# tracer-main.net
KiCad netlist of a schematic drawn in EAGLE
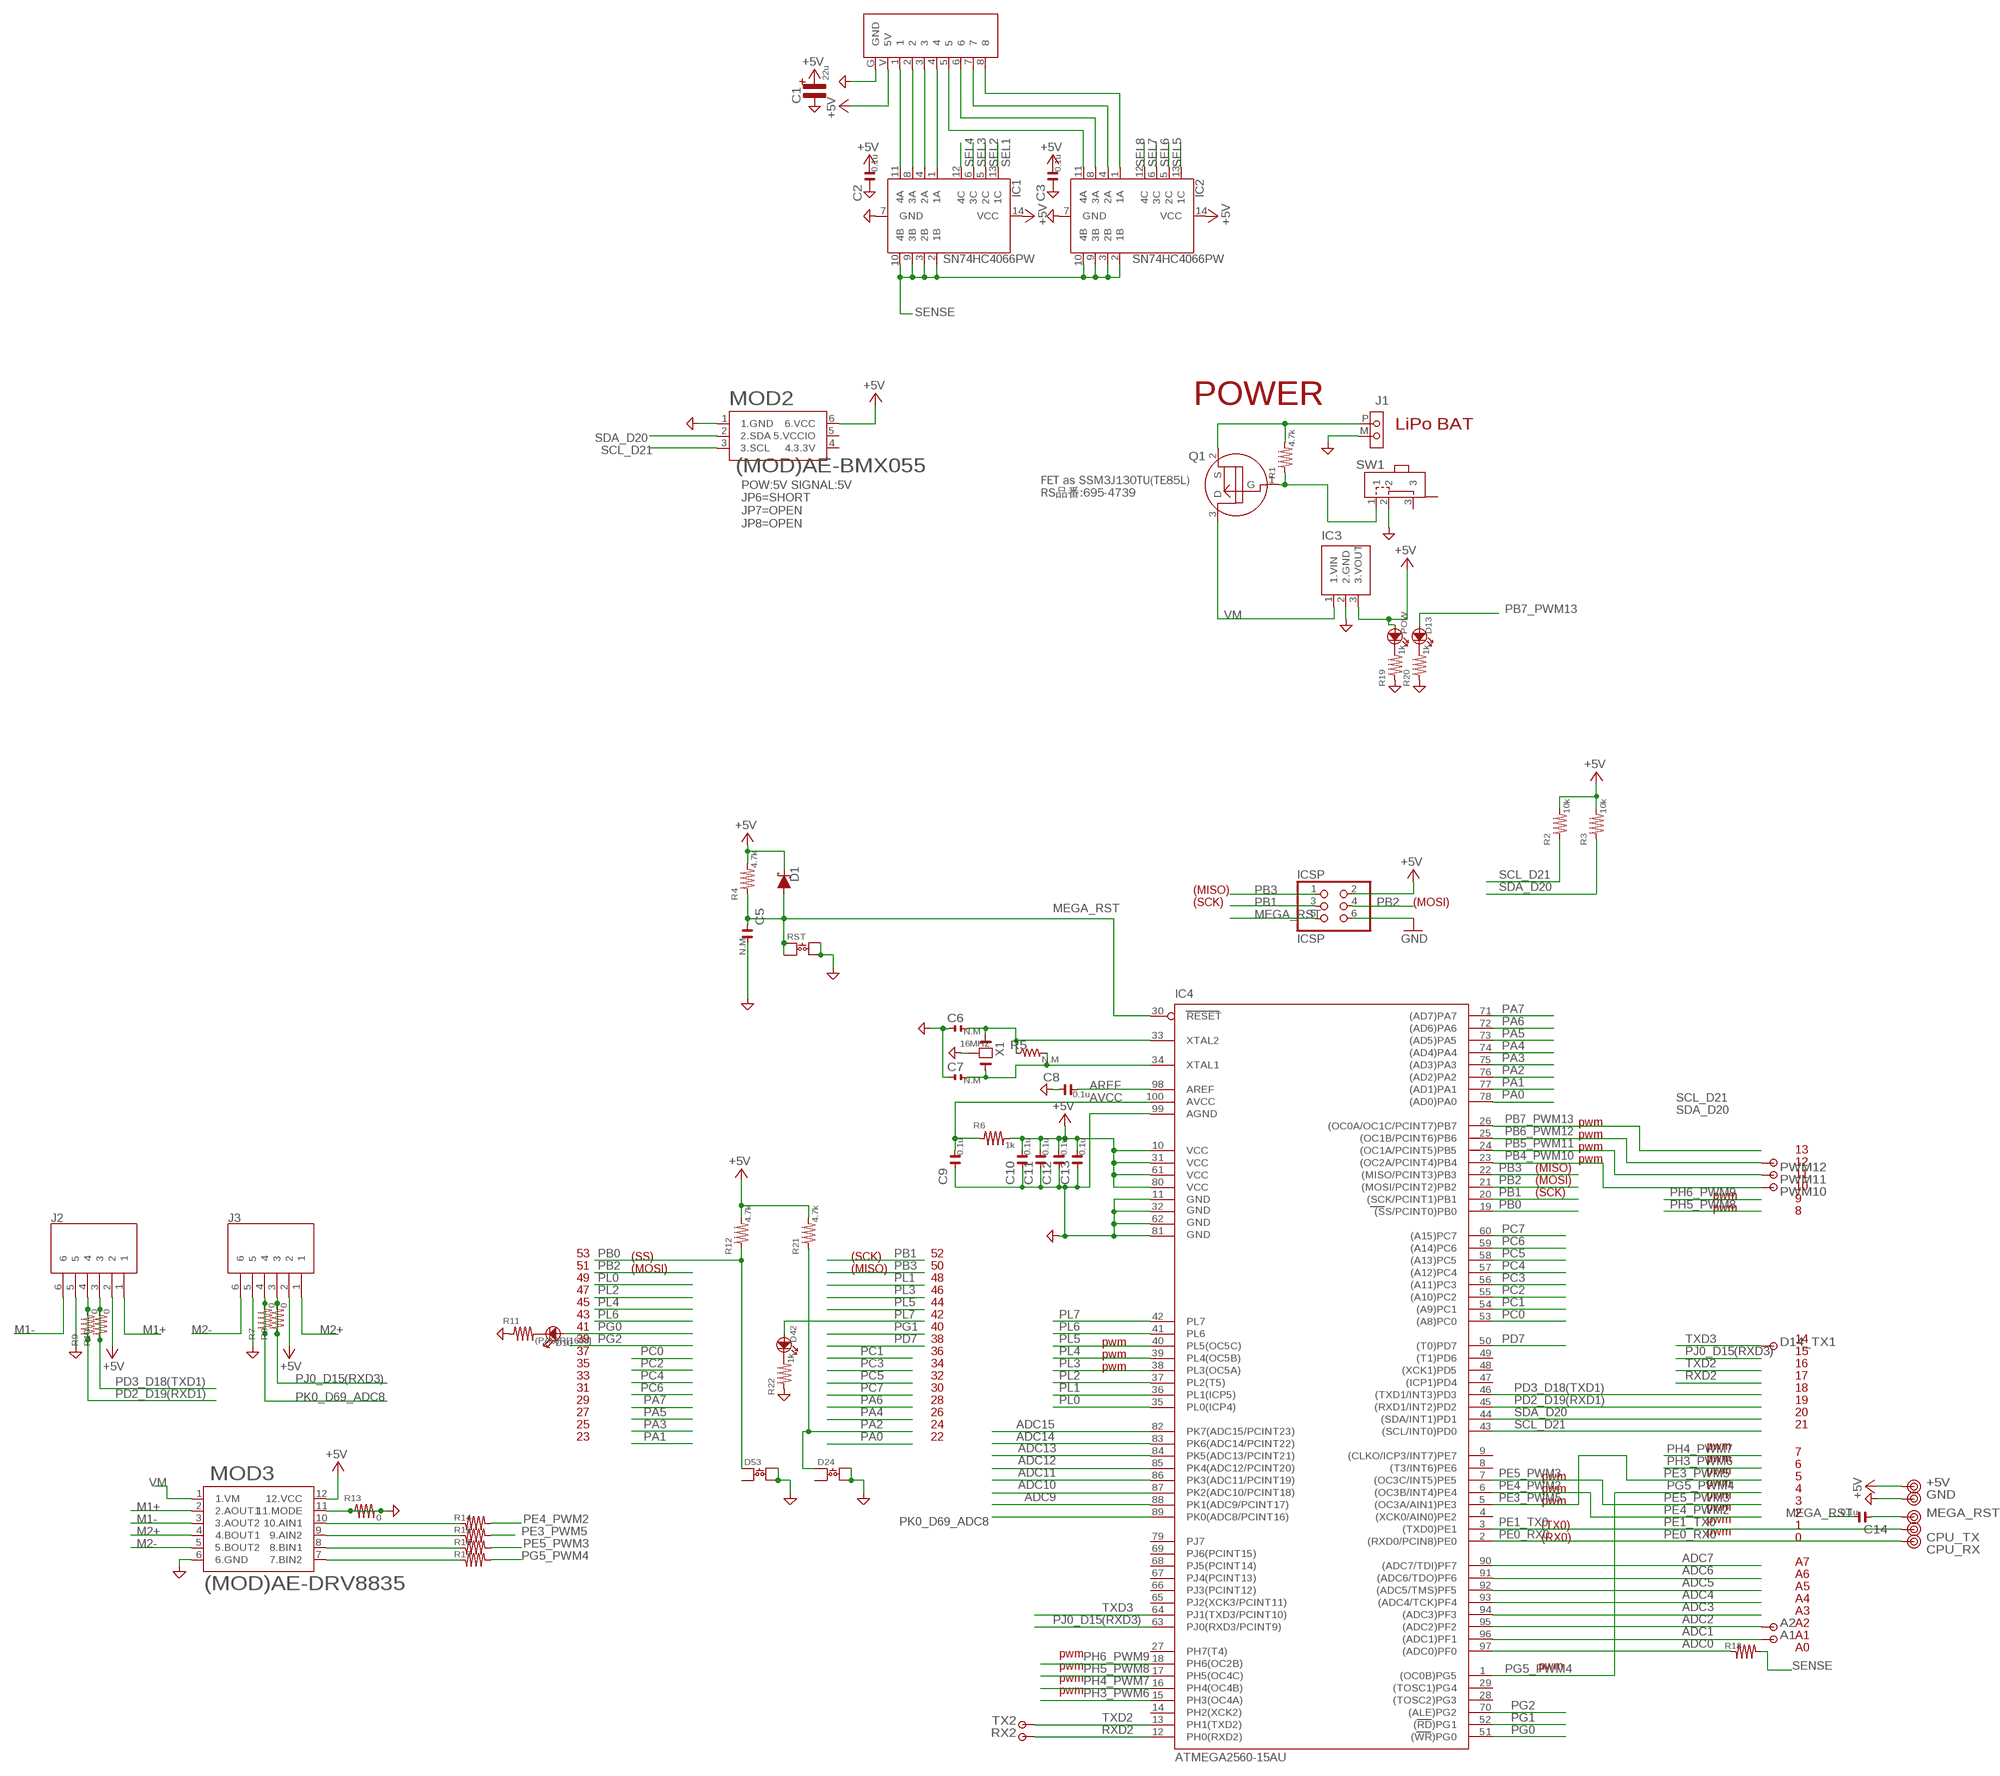
[diagram p0: schematic, sheet 1]

(export (version "E")
  (design (tool "Eeschema 10.0.6"))
  (components
    (comp (ref "+5V")
      (value "TP-HOLE")
      (footprint "eagle-import:TP-HOLE")
      (libsource (lib "eagle-import") (part "TP-HOLE"))
    )
    (comp (ref "A1")
      (value "TP")
      (footprint "eagle-import:TP-SQUARE")
      (libsource (lib "eagle-import") (part "TP"))
    )
    (comp (ref "A2")
      (value "TP")
      (footprint "eagle-import:TP-SQUARE")
      (libsource (lib "eagle-import") (part "TP"))
    )
    (comp (ref "C1")
      (value "22u")
      (footprint "eagle-import:3216")
      (libsource (lib "eagle-import") (part "(PAS)C[3216]"))
    )
    (comp (ref "C2")
      (value "0.1u")
      (footprint "eagle-import:1608NEW")
      (libsource (lib "eagle-import") (part "(PAS)C[1608]"))
    )
    (comp (ref "C3")
      (value "0.1u")
      (footprint "eagle-import:1608NEW")
      (libsource (lib "eagle-import") (part "(PAS)C[1608]"))
    )
    (comp (ref "C5")
      (value "N.M")
      (footprint "eagle-import:1608NEW")
      (libsource (lib "eagle-import") (part "(PAS)C[1608]"))
    )
    (comp (ref "C6")
      (value "N.M")
      (footprint "eagle-import:1005")
      (libsource (lib "eagle-import") (part "C(1005)"))
    )
    (comp (ref "C7")
      (value "N.M")
      (footprint "eagle-import:1005")
      (libsource (lib "eagle-import") (part "C(1005)"))
    )
    (comp (ref "C8")
      (value "0.1u")
      (footprint "eagle-import:1608NEW")
      (libsource (lib "eagle-import") (part "(PAS)C[1608]"))
    )
    (comp (ref "C9")
      (value "0.1u")
      (footprint "eagle-import:1608NEW")
      (libsource (lib "eagle-import") (part "(PAS)C[1608]"))
    )
    (comp (ref "C10")
      (value "0.1u")
      (footprint "eagle-import:1608NEW")
      (libsource (lib "eagle-import") (part "(PAS)C[1608]"))
    )
    (comp (ref "C11")
      (value "0.1u")
      (footprint "eagle-import:1608NEW")
      (libsource (lib "eagle-import") (part "(PAS)C[1608]"))
    )
    (comp (ref "C12")
      (value "0.1u")
      (footprint "eagle-import:1608NEW")
      (libsource (lib "eagle-import") (part "(PAS)C[1608]"))
    )
    (comp (ref "C13")
      (value "0.1u")
      (footprint "eagle-import:1608NEW")
      (libsource (lib "eagle-import") (part "(PAS)C[1608]"))
    )
    (comp (ref "C14")
      (value "0.1u")
      (footprint "eagle-import:1608NEW")
      (libsource (lib "eagle-import") (part "(PAS)C[1608]"))
    )
    (comp (ref "CPU_RX")
      (value "TP-HOLE")
      (footprint "eagle-import:TP-HOLE")
      (libsource (lib "eagle-import") (part "TP-HOLE"))
    )
    (comp (ref "CPU_TX")
      (value "TP-HOLE")
      (footprint "eagle-import:TP-HOLE")
      (libsource (lib "eagle-import") (part "TP-HOLE"))
    )
    (comp (ref "D1")
      (value "1A/23V/620mV")
      (footprint "eagle-import:SOD-323")
      (libsource (lib "eagle-import") (part "DIODE-SCHOTTKY-BAT20J"))
    )
    (comp (ref "D10")
      (value "(PAS)LED[1608]")
      (footprint "eagle-import:1608LED")
      (libsource (lib "eagle-import") (part "(PAS)LED[1608]"))
    )
    (comp (ref "D13")
      (value "(PAS)LED[1608]")
      (footprint "eagle-import:1608LED")
      (libsource (lib "eagle-import") (part "(PAS)LED[1608]"))
    )
    (comp (ref "D14_TX1")
      (value "TP")
      (footprint "eagle-import:TP-SQUARE")
      (libsource (lib "eagle-import") (part "TP"))
    )
    (comp (ref "D24")
      (value "(SW)USER_SW(AKIDUKI)")
      (footprint "eagle-import:SKRPACE010-PAC")
      (libsource (lib "eagle-import") (part "(SW)USER_SW(AKIDUKI)"))
    )
    (comp (ref "D42")
      (value "(PAS)LED[1608]")
      (footprint "eagle-import:1608LED")
      (libsource (lib "eagle-import") (part "(PAS)LED[1608]"))
    )
    (comp (ref "D53")
      (value "(SW)USER_SW(AKIDUKI)")
      (footprint "eagle-import:SKRPACE010-PAC")
      (libsource (lib "eagle-import") (part "(SW)USER_SW(AKIDUKI)"))
    )
    (comp (ref "GND")
      (value "TP-HOLE")
      (footprint "eagle-import:TP-HOLE")
      (libsource (lib "eagle-import") (part "TP-HOLE"))
    )
    (comp (ref "IC1")
      (value "SN74HC4066PW")
      (footprint "eagle-import:SOP65P640X120-14N")
      (fields (field (name "RS_PART_NUMBER") "6622738P"))
      (libsource (lib "eagle-import") (part "SN74HC4066PW"))
    )
    (comp (ref "IC2")
      (value "SN74HC4066PW")
      (footprint "eagle-import:SOP65P640X120-14N")
      (fields (field (name "RS_PART_NUMBER") "6622738P"))
      (libsource (lib "eagle-import") (part "SN74HC4066PW"))
    )
    (comp (ref "IC3")
      (value "(3.3V)VX07803-500")
      (footprint "eagle-import:VX07803-PAC")
      (libsource (lib "eagle-import") (part "(3.3V)VX07803-500"))
    )
    (comp (ref "IC4")
      (value "ATMEGA2560-15AU")
      (footprint "eagle-import:TQFP100")
      (fields (field (name "PART_NUMBER") "ATMEGA2560-16AU"))
      (libsource (lib "eagle-import") (part "0023_ATMEGA2560-16AU"))
    )
    (comp (ref "ICSP")
      (value "ICSP")
      (footprint "eagle-import:2X03")
      (fields (field (name "PART_NUMBER") "PH254-203DF118A00V"))
      (libsource (lib "eagle-import") (part "0114_PH254-203DF118A00V"))
    )
    (comp (ref "J1")
      (value "B2B-PH")
      (footprint "eagle-import:B2B-PH-PAC")
      (libsource (lib "eagle-import") (part "B2B-PH"))
    )
    (comp (ref "J2")
      (value "B6B-ZR-3.4_LF__SN_")
      (footprint "eagle-import:B6BZR34LFSN")
      (fields (field (name "MANUFACTURER_PART_NUMBER") "B6B-ZR-3.4(LF)(SN)"))
      (libsource (lib "eagle-import") (part "B6B-ZR-3.4_LF__SN_"))
    )
    (comp (ref "J3")
      (value "B6B-ZR-3.4_LF__SN_")
      (footprint "eagle-import:B6BZR34LFSN")
      (fields (field (name "MANUFACTURER_PART_NUMBER") "B6B-ZR-3.4(LF)(SN)"))
      (libsource (lib "eagle-import") (part "B6B-ZR-3.4_LF__SN_"))
    )
    (comp (ref "MEGA_RST")
      (value "TP-HOLE")
      (footprint "eagle-import:TP-HOLE")
      (libsource (lib "eagle-import") (part "TP-HOLE"))
    )
    (comp (ref "MOD1")
      (value "(MOD)LINE-TRACER")
      (footprint "eagle-import:8CH-LINETRACER-MOD")
      (libsource (lib "eagle-import") (part "(MOD)LINE-TRACER"))
    )
    (comp (ref "MOD2")
      (value "(MOD)AE-BMX055")
      (footprint "eagle-import:MOD-BMX055")
      (libsource (lib "eagle-import") (part "(MOD)AE-BMX055"))
    )
    (comp (ref "MOD3")
      (value "(MOD)AE-DRV8835")
      (footprint "eagle-import:AE-DRV8835")
      (libsource (lib "eagle-import") (part "(MOD)AE-DRV8835"))
    )
    (comp (ref "POW")
      (value "(PAS)LED[1608]")
      (footprint "eagle-import:1608LED")
      (libsource (lib "eagle-import") (part "(PAS)LED[1608]"))
    )
    (comp (ref "PWM10")
      (value "TP")
      (footprint "eagle-import:TP-SQUARE")
      (libsource (lib "eagle-import") (part "TP"))
    )
    (comp (ref "PWM11")
      (value "TP")
      (footprint "eagle-import:TP-SQUARE")
      (libsource (lib "eagle-import") (part "TP"))
    )
    (comp (ref "PWM12")
      (value "TP")
      (footprint "eagle-import:TP-SQUARE")
      (libsource (lib "eagle-import") (part "TP"))
    )
    (comp (ref "Q1")
      (value "FET-PCH(SSM3J130TU)")
      (footprint "eagle-import:SOT65P210X75-3N")
      (fields
        (field (name "MANUFACTURER_PART_NUMBER") "SSM3J130TU(TE85L)")
        (field (name "RS_PART_NUMBER") "6954739")
      )
      (libsource (lib "eagle-import") (part "FET-PCH(SSM3J130TU)"))
    )
    (comp (ref "R1")
      (value "4.7k")
      (footprint "eagle-import:1608NEW")
      (libsource (lib "eagle-import") (part "(PAS)R[1608]"))
    )
    (comp (ref "R2")
      (value "10k")
      (footprint "eagle-import:1608NEW")
      (libsource (lib "eagle-import") (part "(PAS)R[1608]"))
    )
    (comp (ref "R3")
      (value "10k")
      (footprint "eagle-import:1608NEW")
      (libsource (lib "eagle-import") (part "(PAS)R[1608]"))
    )
    (comp (ref "R4")
      (value "4.7k")
      (footprint "eagle-import:1608NEW")
      (libsource (lib "eagle-import") (part "(PAS)R[1608]"))
    )
    (comp (ref "R5")
      (value "N.M")
      (footprint "eagle-import:1005")
      (libsource (lib "eagle-import") (part "R(1005)"))
    )
    (comp (ref "R6")
      (value "1k")
      (footprint "eagle-import:1608NEW")
      (libsource (lib "eagle-import") (part "(PAS)R[1608]"))
    )
    (comp (ref "R7")
      (value "0")
      (footprint "eagle-import:1608NEW")
      (libsource (lib "eagle-import") (part "(PAS)R[1608]"))
    )
    (comp (ref "R8")
      (value "0")
      (footprint "eagle-import:1608NEW")
      (libsource (lib "eagle-import") (part "(PAS)R[1608]"))
    )
    (comp (ref "R9")
      (value "0")
      (footprint "eagle-import:1608NEW")
      (libsource (lib "eagle-import") (part "(PAS)R[1608]"))
    )
    (comp (ref "R10")
      (value "0")
      (footprint "eagle-import:1608NEW")
      (libsource (lib "eagle-import") (part "(PAS)R[1608]"))
    )
    (comp (ref "R11")
      (value "(PAS)R[1608]")
      (footprint "eagle-import:1608NEW")
      (libsource (lib "eagle-import") (part "(PAS)R[1608]"))
    )
    (comp (ref "R12")
      (value "4.7k")
      (footprint "eagle-import:1608NEW")
      (libsource (lib "eagle-import") (part "(PAS)R[1608]"))
    )
    (comp (ref "R13")
      (value "0")
      (footprint "eagle-import:1608NEW")
      (libsource (lib "eagle-import") (part "(PAS)R[1608]"))
    )
    (comp (ref "R14")
      (value "30")
      (footprint "eagle-import:1608NEW")
      (libsource (lib "eagle-import") (part "(PAS)R[1608]"))
    )
    (comp (ref "R15")
      (value "30")
      (footprint "eagle-import:1608NEW")
      (libsource (lib "eagle-import") (part "(PAS)R[1608]"))
    )
    (comp (ref "R16")
      (value "30")
      (footprint "eagle-import:1608NEW")
      (libsource (lib "eagle-import") (part "(PAS)R[1608]"))
    )
    (comp (ref "R17")
      (value "30")
      (footprint "eagle-import:1608NEW")
      (libsource (lib "eagle-import") (part "(PAS)R[1608]"))
    )
    (comp (ref "R18")
      (value "30")
      (footprint "eagle-import:1608NEW")
      (libsource (lib "eagle-import") (part "(PAS)R[1608]"))
    )
    (comp (ref "R19")
      (value "1k")
      (footprint "eagle-import:1608NEW")
      (libsource (lib "eagle-import") (part "(PAS)R[1608]"))
    )
    (comp (ref "R20")
      (value "1k")
      (footprint "eagle-import:1608NEW")
      (libsource (lib "eagle-import") (part "(PAS)R[1608]"))
    )
    (comp (ref "R21")
      (value "4.7k")
      (footprint "eagle-import:1608NEW")
      (libsource (lib "eagle-import") (part "(PAS)R[1608]"))
    )
    (comp (ref "R22")
      (value "1k")
      (footprint "eagle-import:1608NEW")
      (libsource (lib "eagle-import") (part "(PAS)R[1608]"))
    )
    (comp (ref "RST")
      (value "(SW)USER_SW(AKIDUKI)")
      (footprint "eagle-import:SKRPACE010-PAC")
      (libsource (lib "eagle-import") (part "(SW)USER_SW(AKIDUKI)"))
    )
    (comp (ref "RX2")
      (value "TP")
      (footprint "eagle-import:TP-SQUARE")
      (libsource (lib "eagle-import") (part "TP"))
    )
    (comp (ref "SW1")
      (value "MSK12C01")
      (footprint "eagle-import:MSK12C01")
      (libsource (lib "eagle-import") (part "MSK12C01"))
    )
    (comp (ref "TX2")
      (value "TP")
      (footprint "eagle-import:TP-SQUARE")
      (libsource (lib "eagle-import") (part "TP"))
    )
    (comp (ref "X1")
      (value "16MHZ")
      (footprint "eagle-import:AWSCR8")
      (libsource (lib "eagle-import") (part "(RESONATOR)CSTCE_10_12_16_20MHZ"))
    )
  )
  (nets
    (net (code "1") (name "+5V") (class "Default")
      (node (ref "+5V") (pin "1") (pinfunction "P$1_1") (pintype "passive"))
      (node (ref "C1") (pin "1") (pinfunction "P_1") (pintype "passive"))
      (node (ref "C10") (pin "2") (pinfunction "P$2_2") (pintype "passive"))
      (node (ref "C11") (pin "2") (pinfunction "P$2_2") (pintype "passive"))
      (node (ref "C12") (pin "2") (pinfunction "P$2_2") (pintype "passive"))
      (node (ref "C13") (pin "2") (pinfunction "P$2_2") (pintype "passive"))
      (node (ref "C2") (pin "2") (pinfunction "P$2_2") (pintype "passive"))
      (node (ref "C3") (pin "2") (pinfunction "P$2_2") (pintype "passive"))
      (node (ref "D1") (pin "C") (pinfunction "C_C") (pintype "passive"))
      (node (ref "IC1") (pin "14") (pinfunction "VCC_14") (pintype "passive"))
      (node (ref "IC2") (pin "14") (pinfunction "VCC_14") (pintype "passive"))
      (node (ref "IC3") (pin "3") (pinfunction "3.VOUT_3") (pintype "passive"))
      (node (ref "IC4") (pin "10") (pinfunction "VCC_10") (pintype "power_in"))
      (node (ref "IC4") (pin "31") (pinfunction "VCC1_31") (pintype "power_in"))
      (node (ref "IC4") (pin "61") (pinfunction "VCC2_61") (pintype "power_in"))
      (node (ref "IC4") (pin "80") (pinfunction "VCC3_80") (pintype "power_in"))
      (node (ref "ICSP") (pin "2") (pinfunction "2_2") (pintype "passive"))
      (node (ref "J2") (pin "2") (pinfunction "2_2") (pintype "bidirectional"))
      (node (ref "J3") (pin "2") (pinfunction "2_2") (pintype "bidirectional"))
      (node (ref "MOD1") (pin "V") (pinfunction "5V_V") (pintype "passive"))
      (node (ref "MOD2") (pin "6") (pinfunction "6.VCC_6") (pintype "passive"))
      (node (ref "MOD3") (pin "12") (pinfunction "12.VCC_12") (pintype "passive"))
      (node (ref "POW") (pin "1") (pinfunction "+_1") (pintype "passive"))
      (node (ref "R12") (pin "2") (pinfunction "2_2") (pintype "passive"))
      (node (ref "R2") (pin "2") (pinfunction "2_2") (pintype "passive"))
      (node (ref "R21") (pin "2") (pinfunction "2_2") (pintype "passive"))
      (node (ref "R3") (pin "2") (pinfunction "2_2") (pintype "passive"))
      (node (ref "R4") (pin "2") (pinfunction "2_2") (pintype "passive"))
      (node (ref "R6") (pin "2") (pinfunction "2_2") (pintype "passive"))
    )
    (net (code "2") (name "/ADC0") (class "Default")
      (node (ref "IC4") (pin "97") (pinfunction "(ADC0)PF0_97") (pintype "bidirectional"))
      (node (ref "R18") (pin "1") (pinfunction "1_1") (pintype "passive"))
    )
    (net (code "3") (name "/ADC1") (class "Default")
      (node (ref "A1") (pin "1") (pinfunction "P$1_1") (pintype "passive"))
      (node (ref "IC4") (pin "96") (pinfunction "(ADC1)PF1_96") (pintype "bidirectional"))
    )
    (net (code "4") (name "/ADC2") (class "Default")
      (node (ref "A2") (pin "1") (pinfunction "P$1_1") (pintype "passive"))
      (node (ref "IC4") (pin "95") (pinfunction "(ADC2)PF2_95") (pintype "bidirectional"))
    )
    (net (code "5") (name "/ADC3") (class "Default")
      (node (ref "IC4") (pin "94") (pinfunction "(ADC3)PF3_94") (pintype "bidirectional"))
    )
    (net (code "6") (name "/ADC4") (class "Default")
      (node (ref "IC4") (pin "93") (pinfunction "(ADC4/TCK)PF4_93") (pintype "bidirectional"))
    )
    (net (code "7") (name "/ADC5") (class "Default")
      (node (ref "IC4") (pin "92") (pinfunction "(ADC5/TMS)PF5_92") (pintype "bidirectional"))
    )
    (net (code "8") (name "/ADC6") (class "Default")
      (node (ref "IC4") (pin "91") (pinfunction "(ADC6/TDO)PF6_91") (pintype "bidirectional"))
    )
    (net (code "9") (name "/ADC7") (class "Default")
      (node (ref "IC4") (pin "90") (pinfunction "(ADC7/TDI)PF7_90") (pintype "bidirectional"))
    )
    (net (code "10") (name "/ADC9") (class "Default")
      (node (ref "IC4") (pin "88") (pinfunction "PK1(ADC9/PCINT17)_88") (pintype "bidirectional"))
    )
    (net (code "11") (name "/ADC10") (class "Default")
      (node (ref "IC4") (pin "87") (pinfunction "PK2(ADC10/PCINT18)_87") (pintype "bidirectional"))
    )
    (net (code "12") (name "/ADC11") (class "Default")
      (node (ref "IC4") (pin "86") (pinfunction "PK3(ADC11/PCINT19)_86") (pintype "bidirectional"))
    )
    (net (code "13") (name "/ADC12") (class "Default")
      (node (ref "IC4") (pin "85") (pinfunction "PK4(ADC12/PCINT20)_85") (pintype "bidirectional"))
    )
    (net (code "14") (name "/ADC13") (class "Default")
      (node (ref "IC4") (pin "84") (pinfunction "PK5(ADC13/PCINT21)_84") (pintype "bidirectional"))
    )
    (net (code "15") (name "/ADC14") (class "Default")
      (node (ref "IC4") (pin "83") (pinfunction "PK6(ADC14/PCINT22)_83") (pintype "bidirectional"))
    )
    (net (code "16") (name "/ADC15") (class "Default")
      (node (ref "IC4") (pin "82") (pinfunction "PK7(ADC15/PCINT23)_82") (pintype "bidirectional"))
    )
    (net (code "17") (name "/AREF") (class "Default")
      (node (ref "C8") (pin "2") (pinfunction "P$2_2") (pintype "passive"))
      (node (ref "IC4") (pin "98") (pinfunction "AREF_98") (pintype "bidirectional"))
    )
    (net (code "18") (name "/AVCC") (class "Default")
      (node (ref "C9") (pin "2") (pinfunction "P$2_2") (pintype "passive"))
      (node (ref "IC4") (pin "100") (pinfunction "AVCC_100") (pintype "power_in"))
      (node (ref "R6") (pin "1") (pinfunction "1_1") (pintype "passive"))
    )
    (net (code "19") (name "/M1+") (class "Default")
      (node (ref "J2") (pin "1") (pinfunction "1_1") (pintype "bidirectional"))
      (node (ref "MOD3") (pin "2") (pinfunction "2.AOUT1_2") (pintype "passive"))
    )
    (net (code "20") (name "/M1-") (class "Default")
      (node (ref "J2") (pin "6") (pinfunction "6_6") (pintype "bidirectional"))
      (node (ref "MOD3") (pin "3") (pinfunction "3.AOUT2_3") (pintype "passive"))
    )
    (net (code "21") (name "/M2+") (class "Default")
      (node (ref "J3") (pin "1") (pinfunction "1_1") (pintype "bidirectional"))
      (node (ref "MOD3") (pin "4") (pinfunction "4.BOUT1_4") (pintype "passive"))
    )
    (net (code "22") (name "/M2-") (class "Default")
      (node (ref "J3") (pin "6") (pinfunction "6_6") (pintype "bidirectional"))
      (node (ref "MOD3") (pin "5") (pinfunction "5.BOUT2_5") (pintype "passive"))
    )
    (net (code "23") (name "/MEGA_RST") (class "Default")
      (node (ref "C14") (pin "2") (pinfunction "P$2_2") (pintype "passive"))
      (node (ref "C5") (pin "1") (pinfunction "P$1_1") (pintype "passive"))
      (node (ref "D1") (pin "A") (pinfunction "A_A") (pintype "passive"))
      (node (ref "IC4") (pin "30") (pinfunction "RESET_30") (pintype "input"))
      (node (ref "ICSP") (pin "5") (pinfunction "5_5") (pintype "passive"))
      (node (ref "R4") (pin "1") (pinfunction "1_1") (pintype "passive"))
      (node (ref "RST") (pin "1") (pinfunction "1_1") (pintype "passive"))
      (node (ref "RST") (pin "3") (pinfunction "3_3") (pintype "passive"))
    )
    (net (code "24") (name "/PA0") (class "Default")
      (node (ref "IC4") (pin "78") (pinfunction "(AD0)PA0_78") (pintype "bidirectional"))
    )
    (net (code "25") (name "/PA1") (class "Default")
      (node (ref "IC4") (pin "77") (pinfunction "(AD1)PA1_77") (pintype "bidirectional"))
    )
    (net (code "26") (name "/PA2") (class "Default")
      (node (ref "D24") (pin "1") (pinfunction "1_1") (pintype "passive"))
      (node (ref "IC4") (pin "76") (pinfunction "(AD2)PA2_76") (pintype "bidirectional"))
      (node (ref "R21") (pin "1") (pinfunction "1_1") (pintype "passive"))
    )
    (net (code "27") (name "/PA3") (class "Default")
      (node (ref "IC4") (pin "75") (pinfunction "(AD3)PA3_75") (pintype "bidirectional"))
    )
    (net (code "28") (name "/PA4") (class "Default")
      (node (ref "IC4") (pin "74") (pinfunction "(AD4)PA4_74") (pintype "bidirectional"))
    )
    (net (code "29") (name "/PA5") (class "Default")
      (node (ref "IC4") (pin "73") (pinfunction "(AD5)PA5_73") (pintype "bidirectional"))
    )
    (net (code "30") (name "/PA6") (class "Default")
      (node (ref "IC4") (pin "72") (pinfunction "(AD6)PA6_72") (pintype "bidirectional"))
    )
    (net (code "31") (name "/PA7") (class "Default")
      (node (ref "IC4") (pin "71") (pinfunction "(AD7)PA7_71") (pintype "bidirectional"))
    )
    (net (code "32") (name "/PB0") (class "Default")
      (node (ref "D53") (pin "1") (pinfunction "1_1") (pintype "passive"))
      (node (ref "IC4") (pin "19") (pinfunction "(SS/PCINT0)PB0_19") (pintype "bidirectional"))
      (node (ref "R12") (pin "1") (pinfunction "1_1") (pintype "passive"))
    )
    (net (code "33") (name "/PB1") (class "Default")
      (node (ref "IC4") (pin "20") (pinfunction "(SCK/PCINT1)PB1_20") (pintype "bidirectional"))
      (node (ref "ICSP") (pin "3") (pinfunction "3_3") (pintype "passive"))
    )
    (net (code "34") (name "/PB2") (class "Default")
      (node (ref "IC4") (pin "21") (pinfunction "(MOSI/PCINT2)PB2_21") (pintype "bidirectional"))
      (node (ref "ICSP") (pin "4") (pinfunction "4_4") (pintype "passive"))
    )
    (net (code "35") (name "/PB3") (class "Default")
      (node (ref "IC4") (pin "22") (pinfunction "(MISO/PCINT3)PB3_22") (pintype "bidirectional"))
      (node (ref "ICSP") (pin "1") (pinfunction "1_1") (pintype "passive"))
    )
    (net (code "36") (name "/PB4_PWM10") (class "Default")
      (node (ref "IC4") (pin "23") (pinfunction "(OC2A/PCINT4)PB4_23") (pintype "bidirectional"))
      (node (ref "PWM10") (pin "1") (pinfunction "P$1_1") (pintype "passive"))
    )
    (net (code "37") (name "/PB5_PWM11") (class "Default")
      (node (ref "IC4") (pin "24") (pinfunction "(OC1A/PCINT5)PB5_24") (pintype "bidirectional"))
      (node (ref "PWM11") (pin "1") (pinfunction "P$1_1") (pintype "passive"))
    )
    (net (code "38") (name "/PB6_PWM12") (class "Default")
      (node (ref "IC4") (pin "25") (pinfunction "(OC1B/PCINT6)PB6_25") (pintype "bidirectional"))
      (node (ref "PWM12") (pin "1") (pinfunction "P$1_1") (pintype "passive"))
    )
    (net (code "39") (name "/PB7_PWM13") (class "Default")
      (node (ref "D13") (pin "1") (pinfunction "+_1") (pintype "passive"))
      (node (ref "IC4") (pin "26") (pinfunction "(OC0A/OC1C/PCINT7)PB7_26") (pintype "bidirectional"))
    )
    (net (code "40") (name "/PC0") (class "Default")
      (node (ref "IC4") (pin "53") (pinfunction "(A8)PC0_53") (pintype "bidirectional"))
    )
    (net (code "41") (name "/PC1") (class "Default")
      (node (ref "IC4") (pin "54") (pinfunction "(A9)PC1_54") (pintype "bidirectional"))
    )
    (net (code "42") (name "/PC2") (class "Default")
      (node (ref "IC4") (pin "55") (pinfunction "(A10)PC2_55") (pintype "bidirectional"))
    )
    (net (code "43") (name "/PC3") (class "Default")
      (node (ref "IC4") (pin "56") (pinfunction "(A11)PC3_56") (pintype "bidirectional"))
    )
    (net (code "44") (name "/PC4") (class "Default")
      (node (ref "IC4") (pin "57") (pinfunction "(A12)PC4_57") (pintype "bidirectional"))
    )
    (net (code "45") (name "/PC5") (class "Default")
      (node (ref "IC4") (pin "58") (pinfunction "(A13)PC5_58") (pintype "bidirectional"))
    )
    (net (code "46") (name "/PC6") (class "Default")
      (node (ref "IC4") (pin "59") (pinfunction "(A14)PC6_59") (pintype "bidirectional"))
    )
    (net (code "47") (name "/PC7") (class "Default")
      (node (ref "IC4") (pin "60") (pinfunction "(A15)PC7_60") (pintype "bidirectional"))
    )
    (net (code "48") (name "/PD2_D19(RXD1)") (class "Default")
      (node (ref "IC4") (pin "45") (pinfunction "(RXD1/INT2)PD2_45") (pintype "bidirectional"))
      (node (ref "J2") (pin "4") (pinfunction "4_4") (pintype "bidirectional"))
      (node (ref "R9") (pin "1") (pinfunction "1_1") (pintype "passive"))
      (node (ref "R9") (pin "2") (pinfunction "2_2") (pintype "passive"))
    )
    (net (code "49") (name "/PD3_D18(TXD1)") (class "Default")
      (node (ref "IC4") (pin "46") (pinfunction "(TXD1/INT3)PD3_46") (pintype "bidirectional"))
      (node (ref "J2") (pin "3") (pinfunction "3_3") (pintype "bidirectional"))
      (node (ref "R10") (pin "1") (pinfunction "1_1") (pintype "passive"))
      (node (ref "R10") (pin "2") (pinfunction "2_2") (pintype "passive"))
    )
    (net (code "50") (name "/PD7") (class "Default")
      (node (ref "IC4") (pin "50") (pinfunction "(T0)PD7_50") (pintype "bidirectional"))
    )
    (net (code "51") (name "/PE0_RX0") (class "Default")
      (node (ref "CPU_RX") (pin "1") (pinfunction "P$1_1") (pintype "passive"))
      (node (ref "IC4") (pin "2") (pinfunction "(RXD0/PCIN8)PE0_2") (pintype "bidirectional"))
    )
    (net (code "52") (name "/PE1_TX0") (class "Default")
      (node (ref "CPU_TX") (pin "1") (pinfunction "P$1_1") (pintype "passive"))
      (node (ref "IC4") (pin "3") (pinfunction "(TXD0)PE1_3") (pintype "bidirectional"))
    )
    (net (code "53") (name "/PE3_PWM5") (class "Default")
      (node (ref "IC4") (pin "5") (pinfunction "(OC3A/AIN1)PE3_5") (pintype "bidirectional"))
      (node (ref "R15") (pin "2") (pinfunction "2_2") (pintype "passive"))
    )
    (net (code "54") (name "/PE4_PWM2") (class "Default")
      (node (ref "IC4") (pin "6") (pinfunction "(OC3B/INT4)PE4_6") (pintype "bidirectional"))
      (node (ref "R14") (pin "2") (pinfunction "2_2") (pintype "passive"))
    )
    (net (code "55") (name "/PE5_PWM3") (class "Default")
      (node (ref "IC4") (pin "7") (pinfunction "(OC3C/INT5)PE5_7") (pintype "bidirectional"))
      (node (ref "R16") (pin "2") (pinfunction "2_2") (pintype "passive"))
    )
    (net (code "56") (name "/PG0") (class "Default")
      (node (ref "D10") (pin "1") (pinfunction "+_1") (pintype "passive"))
      (node (ref "IC4") (pin "51") (pinfunction "(WR)PG0_51") (pintype "bidirectional"))
    )
    (net (code "57") (name "/PG1") (class "Default")
      (node (ref "IC4") (pin "52") (pinfunction "(RD)PG1_52") (pintype "bidirectional"))
    )
    (net (code "58") (name "/PG2") (class "Default")
      (node (ref "IC4") (pin "70") (pinfunction "(ALE)PG2_70") (pintype "bidirectional"))
    )
    (net (code "59") (name "/PG5_PWM4") (class "Default")
      (node (ref "IC4") (pin "1") (pinfunction "(OC0B)PG5_1") (pintype "bidirectional"))
      (node (ref "R17") (pin "2") (pinfunction "2_2") (pintype "passive"))
    )
    (net (code "60") (name "/PH3_PWM6") (class "Default")
      (node (ref "IC4") (pin "15") (pinfunction "PH3(OC4A)_15") (pintype "bidirectional"))
    )
    (net (code "61") (name "/PH4_PWM7") (class "Default")
      (node (ref "IC4") (pin "16") (pinfunction "PH4(OC4B)_16") (pintype "bidirectional"))
    )
    (net (code "62") (name "/PH5_PWM8") (class "Default")
      (node (ref "IC4") (pin "17") (pinfunction "PH5(OC4C)_17") (pintype "bidirectional"))
    )
    (net (code "63") (name "/PH6_PWM9") (class "Default")
      (node (ref "IC4") (pin "18") (pinfunction "PH6(OC2B)_18") (pintype "bidirectional"))
    )
    (net (code "64") (name "/PJ0_D15(RXD3)") (class "Default")
      (node (ref "IC4") (pin "63") (pinfunction "PJ0(RXD3/PCINT9)_63") (pintype "bidirectional"))
      (node (ref "J3") (pin "3") (pinfunction "3_3") (pintype "bidirectional"))
      (node (ref "R8") (pin "1") (pinfunction "1_1") (pintype "passive"))
      (node (ref "R8") (pin "2") (pinfunction "2_2") (pintype "passive"))
    )
    (net (code "65") (name "/PK0_D69_ADC8") (class "Default")
      (node (ref "IC4") (pin "89") (pinfunction "PK0(ADC8/PCINT16)_89") (pintype "bidirectional"))
      (node (ref "J3") (pin "4") (pinfunction "4_4") (pintype "bidirectional"))
      (node (ref "R7") (pin "1") (pinfunction "1_1") (pintype "passive"))
      (node (ref "R7") (pin "2") (pinfunction "2_2") (pintype "passive"))
    )
    (net (code "66") (name "/PL0") (class "Default")
      (node (ref "IC4") (pin "35") (pinfunction "PL0(ICP4)_35") (pintype "bidirectional"))
    )
    (net (code "67") (name "/PL1") (class "Default")
      (node (ref "IC4") (pin "36") (pinfunction "PL1(ICP5)_36") (pintype "bidirectional"))
    )
    (net (code "68") (name "/PL2") (class "Default")
      (node (ref "IC4") (pin "37") (pinfunction "PL2(T5)_37") (pintype "bidirectional"))
    )
    (net (code "69") (name "/PL3") (class "Default")
      (node (ref "IC4") (pin "38") (pinfunction "PL3(OC5A)_38") (pintype "bidirectional"))
    )
    (net (code "70") (name "/PL4") (class "Default")
      (node (ref "IC4") (pin "39") (pinfunction "PL4(OC5B)_39") (pintype "bidirectional"))
    )
    (net (code "71") (name "/PL5") (class "Default")
      (node (ref "IC4") (pin "40") (pinfunction "PL5(OC5C)_40") (pintype "bidirectional"))
    )
    (net (code "72") (name "/PL6") (class "Default")
      (node (ref "IC4") (pin "41") (pinfunction "PL6_41") (pintype "bidirectional"))
    )
    (net (code "73") (name "/PL7") (class "Default")
      (node (ref "D42") (pin "1") (pinfunction "+_1") (pintype "passive"))
      (node (ref "IC4") (pin "42") (pinfunction "PL7_42") (pintype "bidirectional"))
    )
    (net (code "74") (name "/RXD2") (class "Default")
      (node (ref "IC4") (pin "12") (pinfunction "PH0(RXD2)_12") (pintype "bidirectional"))
      (node (ref "RX2") (pin "1") (pinfunction "P$1_1") (pintype "passive"))
    )
    (net (code "75") (name "/SCL_D21") (class "Default")
      (node (ref "IC4") (pin "43") (pinfunction "(SCL/INT0)PD0_43") (pintype "bidirectional"))
      (node (ref "MOD2") (pin "3") (pinfunction "3.SCL_3") (pintype "passive"))
      (node (ref "R2") (pin "1") (pinfunction "1_1") (pintype "passive"))
    )
    (net (code "76") (name "/SDA_D20") (class "Default")
      (node (ref "IC4") (pin "44") (pinfunction "(SDA/INT1)PD1_44") (pintype "bidirectional"))
      (node (ref "MOD2") (pin "2") (pinfunction "2.SDA_2") (pintype "passive"))
      (node (ref "R3") (pin "1") (pinfunction "1_1") (pintype "passive"))
    )
    (net (code "77") (name "/SEL1") (class "Default")
      (node (ref "IC1") (pin "13") (pinfunction "1C_13") (pintype "passive"))
    )
    (net (code "78") (name "/SEL2") (class "Default")
      (node (ref "IC1") (pin "5") (pinfunction "2C_5") (pintype "passive"))
    )
    (net (code "79") (name "/SEL3") (class "Default")
      (node (ref "IC1") (pin "6") (pinfunction "3C_6") (pintype "passive"))
    )
    (net (code "80") (name "/SEL4") (class "Default")
      (node (ref "IC1") (pin "12") (pinfunction "4C_12") (pintype "passive"))
    )
    (net (code "81") (name "/SEL5") (class "Default")
      (node (ref "IC2") (pin "13") (pinfunction "1C_13") (pintype "passive"))
    )
    (net (code "82") (name "/SEL6") (class "Default")
      (node (ref "IC2") (pin "5") (pinfunction "2C_5") (pintype "passive"))
    )
    (net (code "83") (name "/SEL7") (class "Default")
      (node (ref "IC2") (pin "6") (pinfunction "3C_6") (pintype "passive"))
    )
    (net (code "84") (name "/SEL8") (class "Default")
      (node (ref "IC2") (pin "12") (pinfunction "4C_12") (pintype "passive"))
    )
    (net (code "85") (name "/SENSE") (class "Default")
      (node (ref "IC1") (pin "10") (pinfunction "4B_10") (pintype "passive"))
      (node (ref "IC1") (pin "2") (pinfunction "1B_2") (pintype "passive"))
      (node (ref "IC1") (pin "3") (pinfunction "2B_3") (pintype "passive"))
      (node (ref "IC1") (pin "9") (pinfunction "3B_9") (pintype "passive"))
      (node (ref "IC2") (pin "10") (pinfunction "4B_10") (pintype "passive"))
      (node (ref "IC2") (pin "2") (pinfunction "1B_2") (pintype "passive"))
      (node (ref "IC2") (pin "3") (pinfunction "2B_3") (pintype "passive"))
      (node (ref "IC2") (pin "9") (pinfunction "3B_9") (pintype "passive"))
      (node (ref "R18") (pin "2") (pinfunction "2_2") (pintype "passive"))
    )
    (net (code "86") (name "/TXD2") (class "Default")
      (node (ref "IC4") (pin "13") (pinfunction "PH1(TXD2)_13") (pintype "bidirectional"))
      (node (ref "TX2") (pin "1") (pinfunction "P$1_1") (pintype "passive"))
    )
    (net (code "87") (name "/TXD3") (class "Default")
      (node (ref "D14_TX1") (pin "1") (pinfunction "P$1_1") (pintype "passive"))
      (node (ref "IC4") (pin "64") (pinfunction "PJ1(TXD3/PCINT10)_64") (pintype "bidirectional"))
    )
    (net (code "88") (name "/VM") (class "Default")
      (node (ref "IC3") (pin "1") (pinfunction "1.VIN_1") (pintype "passive"))
      (node (ref "MOD3") (pin "1") (pinfunction "1.VM_1") (pintype "passive"))
      (node (ref "Q1") (pin "3") (pinfunction "D_3") (pintype "bidirectional"))
    )
    (net (code "89") (name "GND") (class "Default")
      (node (ref "C1") (pin "2") (pinfunction "M_2") (pintype "passive"))
      (node (ref "C10") (pin "1") (pinfunction "P$1_1") (pintype "passive"))
      (node (ref "C11") (pin "1") (pinfunction "P$1_1") (pintype "passive"))
      (node (ref "C12") (pin "1") (pinfunction "P$1_1") (pintype "passive"))
      (node (ref "C13") (pin "1") (pinfunction "P$1_1") (pintype "passive"))
      (node (ref "C2") (pin "1") (pinfunction "P$1_1") (pintype "passive"))
      (node (ref "C3") (pin "1") (pinfunction "P$1_1") (pintype "passive"))
      (node (ref "C5") (pin "2") (pinfunction "P$2_2") (pintype "passive"))
      (node (ref "C6") (pin "1") (pinfunction "P$1_1") (pintype "passive"))
      (node (ref "C7") (pin "1") (pinfunction "P$1_1") (pintype "passive"))
      (node (ref "C8") (pin "1") (pinfunction "P$1_1") (pintype "passive"))
      (node (ref "C9") (pin "1") (pinfunction "P$1_1") (pintype "passive"))
      (node (ref "D24") (pin "2") (pinfunction "2_2") (pintype "passive"))
      (node (ref "D24") (pin "4") (pinfunction "4_4") (pintype "passive"))
      (node (ref "D53") (pin "2") (pinfunction "2_2") (pintype "passive"))
      (node (ref "D53") (pin "4") (pinfunction "4_4") (pintype "passive"))
      (node (ref "GND") (pin "1") (pinfunction "P$1_1") (pintype "passive"))
      (node (ref "IC1") (pin "7") (pinfunction "GND_7") (pintype "passive"))
      (node (ref "IC2") (pin "7") (pinfunction "GND_7") (pintype "passive"))
      (node (ref "IC3") (pin "2") (pinfunction "2.GND_2") (pintype "passive"))
      (node (ref "IC4") (pin "11") (pinfunction "GND_11") (pintype "power_in"))
      (node (ref "IC4") (pin "32") (pinfunction "GND1_32") (pintype "power_in"))
      (node (ref "IC4") (pin "62") (pinfunction "GND2_62") (pintype "power_in"))
      (node (ref "IC4") (pin "81") (pinfunction "GND3_81") (pintype "power_in"))
      (node (ref "IC4") (pin "99") (pinfunction "AGND_99") (pintype "power_in"))
      (node (ref "ICSP") (pin "6") (pinfunction "6_6") (pintype "passive"))
      (node (ref "J1") (pin "M") (pinfunction "P$1_M") (pintype "passive"))
      (node (ref "J2") (pin "5") (pinfunction "5_5") (pintype "bidirectional"))
      (node (ref "J3") (pin "5") (pinfunction "5_5") (pintype "bidirectional"))
      (node (ref "MOD1") (pin "G") (pinfunction "GND_G") (pintype "passive"))
      (node (ref "MOD2") (pin "1") (pinfunction "1.GND_1") (pintype "passive"))
      (node (ref "MOD3") (pin "11") (pinfunction "11.MODE_11") (pintype "passive"))
      (node (ref "MOD3") (pin "6") (pinfunction "6.GND_6") (pintype "passive"))
      (node (ref "R11") (pin "1") (pinfunction "1_1") (pintype "passive"))
      (node (ref "R13") (pin "1") (pinfunction "1_1") (pintype "passive"))
      (node (ref "R13") (pin "2") (pinfunction "2_2") (pintype "passive"))
      (node (ref "R19") (pin "1") (pinfunction "1_1") (pintype "passive"))
      (node (ref "R20") (pin "1") (pinfunction "1_1") (pintype "passive"))
      (node (ref "R22") (pin "1") (pinfunction "1_1") (pintype "passive"))
      (node (ref "RST") (pin "2") (pinfunction "2_2") (pintype "passive"))
      (node (ref "RST") (pin "4") (pinfunction "4_4") (pintype "passive"))
      (node (ref "SW1") (pin "2") (pinfunction "2_2") (pintype "passive"))
      (node (ref "X1") (pin "2") (pinfunction "2_2") (pintype "passive"))
    )
    (net (code "90") (name "Net-(C6-P$2)") (class "Default")
      (node (ref "C6") (pin "2") (pinfunction "P$2_2") (pintype "passive"))
      (node (ref "IC4") (pin "33") (pinfunction "XTAL2_33") (pintype "output"))
      (node (ref "R5") (pin "1") (pinfunction "1_1") (pintype "passive"))
      (node (ref "X1") (pin "1") (pinfunction "1_1") (pintype "passive"))
    )
    (net (code "91") (name "Net-(C7-P$2)") (class "Default")
      (node (ref "C7") (pin "2") (pinfunction "P$2_2") (pintype "passive"))
      (node (ref "IC4") (pin "34") (pinfunction "XTAL1_34") (pintype "input"))
      (node (ref "R5") (pin "2") (pinfunction "2_2") (pintype "passive"))
      (node (ref "X1") (pin "3") (pinfunction "3_3") (pintype "passive"))
    )
    (net (code "92") (name "Net-(C14-P$1)") (class "Default")
      (node (ref "C14") (pin "1") (pinfunction "P$1_1") (pintype "passive"))
      (node (ref "MEGA_RST") (pin "1") (pinfunction "P$1_1") (pintype "passive"))
    )
    (net (code "93") (name "Net-(D10--)") (class "Default")
      (node (ref "D10") (pin "2") (pinfunction "-_2") (pintype "passive"))
      (node (ref "R11") (pin "2") (pinfunction "2_2") (pintype "passive"))
    )
    (net (code "94") (name "Net-(D13--)") (class "Default")
      (node (ref "D13") (pin "2") (pinfunction "-_2") (pintype "passive"))
      (node (ref "R20") (pin "2") (pinfunction "2_2") (pintype "passive"))
    )
    (net (code "95") (name "Net-(D42--)") (class "Default")
      (node (ref "D42") (pin "2") (pinfunction "-_2") (pintype "passive"))
      (node (ref "R22") (pin "2") (pinfunction "2_2") (pintype "passive"))
    )
    (net (code "96") (name "Net-(IC1-1A)") (class "Default")
      (node (ref "IC1") (pin "1") (pinfunction "1A_1") (pintype "passive"))
      (node (ref "MOD1") (pin "4") (pinfunction "4_4") (pintype "passive"))
    )
    (net (code "97") (name "Net-(IC1-2A)") (class "Default")
      (node (ref "IC1") (pin "4") (pinfunction "2A_4") (pintype "passive"))
      (node (ref "MOD1") (pin "3") (pinfunction "3_3") (pintype "passive"))
    )
    (net (code "98") (name "Net-(IC1-3A)") (class "Default")
      (node (ref "IC1") (pin "8") (pinfunction "3A_8") (pintype "passive"))
      (node (ref "MOD1") (pin "2") (pinfunction "2_2") (pintype "passive"))
    )
    (net (code "99") (name "Net-(IC1-4A)") (class "Default")
      (node (ref "IC1") (pin "11") (pinfunction "4A_11") (pintype "passive"))
      (node (ref "MOD1") (pin "1") (pinfunction "1_1") (pintype "passive"))
    )
    (net (code "100") (name "Net-(IC2-1A)") (class "Default")
      (node (ref "IC2") (pin "1") (pinfunction "1A_1") (pintype "passive"))
      (node (ref "MOD1") (pin "8") (pinfunction "8_8") (pintype "passive"))
    )
    (net (code "101") (name "Net-(IC2-2A)") (class "Default")
      (node (ref "IC2") (pin "4") (pinfunction "2A_4") (pintype "passive"))
      (node (ref "MOD1") (pin "7") (pinfunction "7_7") (pintype "passive"))
    )
    (net (code "102") (name "Net-(IC2-3A)") (class "Default")
      (node (ref "IC2") (pin "8") (pinfunction "3A_8") (pintype "passive"))
      (node (ref "MOD1") (pin "6") (pinfunction "6_6") (pintype "passive"))
    )
    (net (code "103") (name "Net-(IC2-4A)") (class "Default")
      (node (ref "IC2") (pin "11") (pinfunction "4A_11") (pintype "passive"))
      (node (ref "MOD1") (pin "5") (pinfunction "5_5") (pintype "passive"))
    )
    (net (code "104") (name "Net-(J1-P$2)") (class "Default")
      (node (ref "J1") (pin "P") (pinfunction "P$2_P") (pintype "passive"))
      (node (ref "Q1") (pin "2") (pinfunction "S_2") (pintype "bidirectional"))
      (node (ref "R1") (pin "2") (pinfunction "2_2") (pintype "passive"))
    )
    (net (code "105") (name "Net-(MOD3-7.BIN2)") (class "Default")
      (node (ref "MOD3") (pin "7") (pinfunction "7.BIN2_7") (pintype "passive"))
      (node (ref "R17") (pin "1") (pinfunction "1_1") (pintype "passive"))
    )
    (net (code "106") (name "Net-(MOD3-8.BIN1)") (class "Default")
      (node (ref "MOD3") (pin "8") (pinfunction "8.BIN1_8") (pintype "passive"))
      (node (ref "R16") (pin "1") (pinfunction "1_1") (pintype "passive"))
    )
    (net (code "107") (name "Net-(MOD3-9.AIN2)") (class "Default")
      (node (ref "MOD3") (pin "9") (pinfunction "9.AIN2_9") (pintype "passive"))
      (node (ref "R15") (pin "1") (pinfunction "1_1") (pintype "passive"))
    )
    (net (code "108") (name "Net-(MOD3-10.AIN1)") (class "Default")
      (node (ref "MOD3") (pin "10") (pinfunction "10.AIN1_10") (pintype "passive"))
      (node (ref "R14") (pin "1") (pinfunction "1_1") (pintype "passive"))
    )
    (net (code "109") (name "Net-(POW--)") (class "Default")
      (node (ref "POW") (pin "2") (pinfunction "-_2") (pintype "passive"))
      (node (ref "R19") (pin "2") (pinfunction "2_2") (pintype "passive"))
    )
    (net (code "110") (name "Net-(Q1-G)") (class "Default")
      (node (ref "Q1") (pin "1") (pinfunction "G_1") (pintype "bidirectional"))
      (node (ref "R1") (pin "1") (pinfunction "1_1") (pintype "passive"))
      (node (ref "SW1") (pin "1") (pinfunction "1_1") (pintype "passive"))
    )
    (net (code "111") (name "unconnected-(D24-Pad3)") (class "Default")
      (node (ref "D24") (pin "3") (pinfunction "3_3") (pintype "passive"))
    )
    (net (code "112") (name "unconnected-(D53-Pad3)") (class "Default")
      (node (ref "D53") (pin "3") (pinfunction "3_3") (pintype "passive"))
    )
    (net (code "113") (name "unconnected-(IC4-(CLKO{slash}ICP3{slash}INT7)PE7-Pad9)") (class "Default")
      (node (ref "IC4") (pin "9") (pinfunction "(CLKO/ICP3/INT7)PE7_9") (pintype "bidirectional"))
    )
    (net (code "114") (name "unconnected-(IC4-(ICP1)PD4-Pad47)") (class "Default")
      (node (ref "IC4") (pin "47") (pinfunction "(ICP1)PD4_47") (pintype "bidirectional"))
    )
    (net (code "115") (name "unconnected-(IC4-(T1)PD6-Pad49)") (class "Default")
      (node (ref "IC4") (pin "49") (pinfunction "(T1)PD6_49") (pintype "bidirectional"))
    )
    (net (code "116") (name "unconnected-(IC4-(T3{slash}INT6)PE6-Pad8)") (class "Default")
      (node (ref "IC4") (pin "8") (pinfunction "(T3/INT6)PE6_8") (pintype "bidirectional"))
    )
    (net (code "117") (name "unconnected-(IC4-(TOSC1)PG4-Pad29)") (class "Default")
      (node (ref "IC4") (pin "29") (pinfunction "(TOSC1)PG4_29") (pintype "bidirectional"))
    )
    (net (code "118") (name "unconnected-(IC4-(TOSC2)PG3-Pad28)") (class "Default")
      (node (ref "IC4") (pin "28") (pinfunction "(TOSC2)PG3_28") (pintype "bidirectional"))
    )
    (net (code "119") (name "unconnected-(IC4-(XCK0{slash}AIN0)PE2-Pad4)") (class "Default")
      (node (ref "IC4") (pin "4") (pinfunction "(XCK0/AIN0)PE2_4") (pintype "bidirectional"))
    )
    (net (code "120") (name "unconnected-(IC4-(XCK1)PD5-Pad48)") (class "Default")
      (node (ref "IC4") (pin "48") (pinfunction "(XCK1)PD5_48") (pintype "bidirectional"))
    )
    (net (code "121") (name "unconnected-(IC4-PH2(XCK2)-Pad14)") (class "Default")
      (node (ref "IC4") (pin "14") (pinfunction "PH2(XCK2)_14") (pintype "bidirectional"))
    )
    (net (code "122") (name "unconnected-(IC4-PH7(T4)-Pad27)") (class "Default")
      (node (ref "IC4") (pin "27") (pinfunction "PH7(T4)_27") (pintype "bidirectional"))
    )
    (net (code "123") (name "unconnected-(IC4-PJ2(XCK3{slash}PCINT11)-Pad65)") (class "Default")
      (node (ref "IC4") (pin "65") (pinfunction "PJ2(XCK3/PCINT11)_65") (pintype "bidirectional"))
    )
    (net (code "124") (name "unconnected-(IC4-PJ3(PCINT12)-Pad66)") (class "Default")
      (node (ref "IC4") (pin "66") (pinfunction "PJ3(PCINT12)_66") (pintype "bidirectional"))
    )
    (net (code "125") (name "unconnected-(IC4-PJ4(PCINT13)-Pad67)") (class "Default")
      (node (ref "IC4") (pin "67") (pinfunction "PJ4(PCINT13)_67") (pintype "bidirectional"))
    )
    (net (code "126") (name "unconnected-(IC4-PJ5(PCINT14)-Pad68)") (class "Default")
      (node (ref "IC4") (pin "68") (pinfunction "PJ5(PCINT14)_68") (pintype "bidirectional"))
    )
    (net (code "127") (name "unconnected-(IC4-PJ6(PCINT15)-Pad69)") (class "Default")
      (node (ref "IC4") (pin "69") (pinfunction "PJ6(PCINT15)_69") (pintype "bidirectional"))
    )
    (net (code "128") (name "unconnected-(IC4-PJ7-Pad79)") (class "Default")
      (node (ref "IC4") (pin "79") (pinfunction "PJ7_79") (pintype "bidirectional"))
    )
    (net (code "129") (name "unconnected-(MOD2-4.3.3V-Pad4)") (class "Default")
      (node (ref "MOD2") (pin "4") (pinfunction "4.3.3V_4") (pintype "passive"))
    )
    (net (code "130") (name "unconnected-(MOD2-5.VCCIO-Pad5)") (class "Default")
      (node (ref "MOD2") (pin "5") (pinfunction "5.VCCIO_5") (pintype "passive"))
    )
    (net (code "131") (name "unconnected-(SW1-Pad3)") (class "Default")
      (node (ref "SW1") (pin "3") (pinfunction "3_3") (pintype "passive"))
    )
    (net (code "132") (name "unconnected-(SW1-Pad4)") (class "Default")
      (node (ref "SW1") (pin "4") (pinfunction "4_4") (pintype "passive"))
    )
  )
)
